# PCB-GONIO-V2.net
KiCad netlist of a schematic drawn in EAGLE
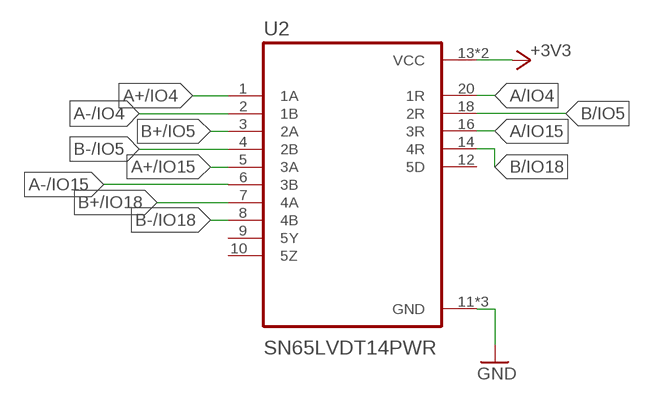
[diagram p0: schematic, sheet 1, part 1 of 2]
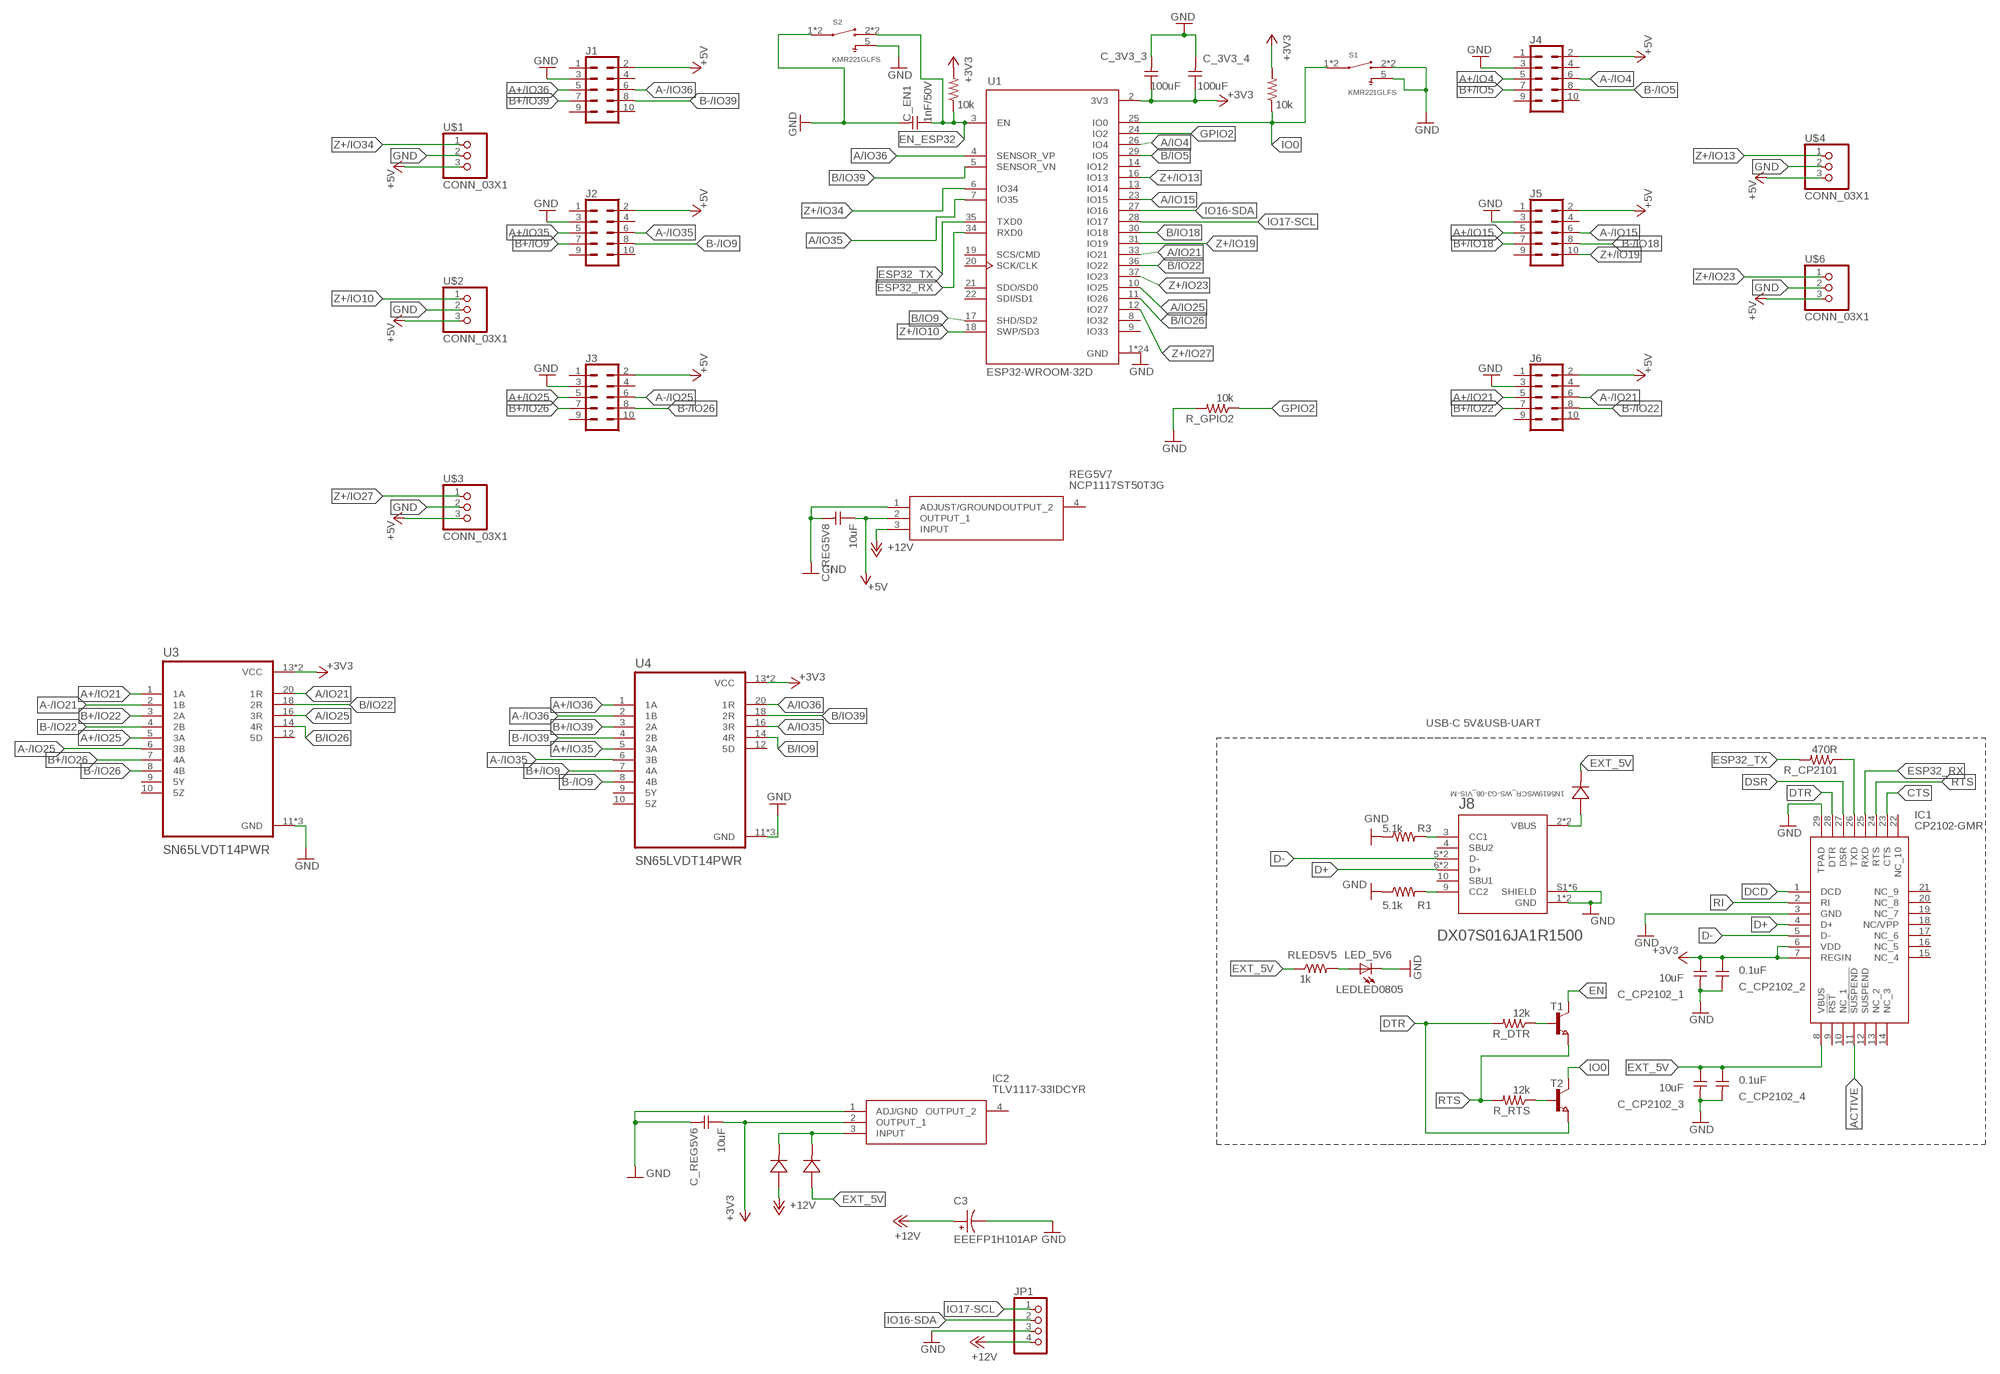
[diagram p1: schematic, sheet 1, part 2 of 2]

(export (version "E")
  (design (tool "Eeschema 10.0.6"))
  (components
    (comp (ref "C3")
      (value "EEEFP1H101AP")
      (footprint "eagle-import:CAP_EEEFP1H101AP")
      (fields (field (name "DIGIKEY_PART_NUMBER") "P19726TR-ND") (field (name "MF") "Panasonic"))
      (libsource (lib "eagle-import") (part "EEEFP1H101AP"))
    )
    (comp (ref "CR1")
      (value "1N5819WSCR_WS-G3-08_VIS-M")
      (footprint "eagle-import:CR_WS-G3-08_VIS-M")
      (fields
        (field (name "MANUFACTURER_PART_NUMBER") "1N4148WS-G3-08")
        (field (name "COPYRIGHT") "Copyright (C) 2022 Ultra Librarian. All rights reserved.")
      )
      (libsource (lib "eagle-import") (part "1N5819WSCR_WS-G3-08_VIS-M"))
    )
    (comp (ref "CR2")
      (value "1N5819WSCR_WS-G3-08_VIS-M")
      (footprint "eagle-import:CR_WS-G3-08_VIS-M")
      (fields
        (field (name "MANUFACTURER_PART_NUMBER") "1N4148WS-G3-08")
        (field (name "COPYRIGHT") "Copyright (C) 2022 Ultra Librarian. All rights reserved.")
      )
      (libsource (lib "eagle-import") (part "1N5819WSCR_WS-G3-08_VIS-M"))
    )
    (comp (ref "CR3")
      (value "1N5819WSCR_WS-G3-08_VIS-M")
      (footprint "eagle-import:CR_WS-G3-08_VIS-M")
      (fields
        (field (name "MANUFACTURER_PART_NUMBER") "1N4148WS-G3-08")
        (field (name "COPYRIGHT") "Copyright (C) 2022 Ultra Librarian. All rights reserved.")
      )
      (libsource (lib "eagle-import") (part "1N5819WSCR_WS-G3-08_VIS-M"))
    )
    (comp (ref "C_3V3_3")
      (value "100uF")
      (footprint "eagle-import:C1206FAB")
      (libsource (lib "eagle-import") (part "CAP_UNPOLARIZEDFAB"))
    )
    (comp (ref "C_3V3_4")
      (value "100uF")
      (footprint "eagle-import:C1206FAB")
      (libsource (lib "eagle-import") (part "CAP_UNPOLARIZEDFAB"))
    )
    (comp (ref "C_CP2102_1")
      (value "10uF")
      (footprint "eagle-import:C1206FAB")
      (libsource (lib "eagle-import") (part "CAP_UNPOLARIZEDFAB"))
    )
    (comp (ref "C_CP2102_2")
      (value "0.1uF")
      (footprint "eagle-import:C1206FAB")
      (libsource (lib "eagle-import") (part "CAP_UNPOLARIZEDFAB"))
    )
    (comp (ref "C_CP2102_3")
      (value "10uF")
      (footprint "eagle-import:C1206FAB")
      (libsource (lib "eagle-import") (part "CAP_UNPOLARIZEDFAB"))
    )
    (comp (ref "C_CP2102_4")
      (value "0.1uF")
      (footprint "eagle-import:C1206FAB")
      (libsource (lib "eagle-import") (part "CAP_UNPOLARIZEDFAB"))
    )
    (comp (ref "C_EN1")
      (value "1nF/50V")
      (footprint "eagle-import:C1206FAB")
      (libsource (lib "eagle-import") (part "CAP_UNPOLARIZEDFAB"))
    )
    (comp (ref "C_REG5V6")
      (value "10uF")
      (footprint "eagle-import:C1206FAB")
      (libsource (lib "eagle-import") (part "CAP_UNPOLARIZEDFAB"))
    )
    (comp (ref "C_REG5V8")
      (value "10uF")
      (footprint "eagle-import:C1206FAB")
      (libsource (lib "eagle-import") (part "CAP_UNPOLARIZEDFAB"))
    )
    (comp (ref "IC1")
      (value "CP2102-GMR")
      (footprint "eagle-import:QFN50P500X500X100-29N")
      (fields (field (name "MOUSER_PART_NUMBER") "634-CP2102-GMR"))
      (libsource (lib "eagle-import") (part "CP2102-GMR"))
    )
    (comp (ref "IC2")
      (value "TLV1117-33IDCYR")
      (footprint "eagle-import:SOT230P700X180-4N")
      (fields (field (name "MOUSER_PART_NUMBER") "595-TLV1117-33IDCYR"))
      (libsource (lib "eagle-import") (part "TLV1117-33IDCYR"))
    )
    (comp (ref "J1")
      (value "CONN_05X2SHD")
      (footprint "eagle-import:2X5-SHROUDED")
      (libsource (lib "eagle-import") (part "CONN_05X2SHD"))
    )
    (comp (ref "J2")
      (value "CONN_05X2SHD")
      (footprint "eagle-import:2X5-SHROUDED")
      (libsource (lib "eagle-import") (part "CONN_05X2SHD"))
    )
    (comp (ref "J3")
      (value "CONN_05X2SHD")
      (footprint "eagle-import:2X5-SHROUDED")
      (libsource (lib "eagle-import") (part "CONN_05X2SHD"))
    )
    (comp (ref "J4")
      (value "CONN_05X2SHD")
      (footprint "eagle-import:2X5-SHROUDED")
      (libsource (lib "eagle-import") (part "CONN_05X2SHD"))
    )
    (comp (ref "J5")
      (value "CONN_05X2SHD")
      (footprint "eagle-import:2X5-SHROUDED")
      (libsource (lib "eagle-import") (part "CONN_05X2SHD"))
    )
    (comp (ref "J6")
      (value "CONN_05X2SHD")
      (footprint "eagle-import:2X5-SHROUDED")
      (libsource (lib "eagle-import") (part "CONN_05X2SHD"))
    )
    (comp (ref "J8")
      (value "DX07S016JA1R1500")
      (footprint "eagle-import:JAE_DX07S016JA1R1500")
      (fields (field (name "MF") "Japan Aviation Electronics"))
      (libsource (lib "eagle-import") (part "DX07S016JA1R1500"))
    )
    (comp (ref "JP1")
      (value "PINHD-1X4")
      (footprint "eagle-import:1X04")
      (libsource (lib "eagle-import") (part "PINHD-1X4"))
    )
    (comp (ref "LED_5V6")
      (value "LEDLED0805")
      (footprint "eagle-import:LEDC2012X90N")
      (libsource (lib "eagle-import") (part "LEDLED0805"))
    )
    (comp (ref "R1")
      (value "5.1k")
      (footprint "eagle-import:R1206W")
      (libsource (lib "eagle-import") (part "R-US_R1206W"))
    )
    (comp (ref "R3")
      (value "5.1k")
      (footprint "eagle-import:R1206W")
      (libsource (lib "eagle-import") (part "R-US_R1206W"))
    )
    (comp (ref "REG5V7")
      (value "NCP1117ST50T3G")
      (footprint "eagle-import:SOT230P700X180-4N")
      (fields (field (name "LCSC_PART") "C17314") (field (name "RS_PART_NUMBER") "8022130P"))
      (libsource (lib "eagle-import") (part "NCP1117ST50T3G"))
    )
    (comp (ref "RLED5V5")
      (value "1k")
      (footprint "eagle-import:R1206FAB")
      (libsource (lib "eagle-import") (part "R1206FAB"))
    )
    (comp (ref "R_CP2101")
      (value "470R")
      (footprint "eagle-import:R1206FAB")
      (libsource (lib "eagle-import") (part "R1206FAB"))
    )
    (comp (ref "R_DTR")
      (value "12k")
      (footprint "eagle-import:R1206FAB")
      (libsource (lib "eagle-import") (part "R1206FAB"))
    )
    (comp (ref "R_GPIO2")
      (value "10k")
      (footprint "eagle-import:R1206FAB")
      (libsource (lib "eagle-import") (part "R1206FAB"))
    )
    (comp (ref "R_PULL_UP1")
      (value "10k")
      (footprint "eagle-import:R1206FAB")
      (libsource (lib "eagle-import") (part "R1206FAB"))
    )
    (comp (ref "R_PULL_UP3")
      (value "10k")
      (footprint "eagle-import:R1206FAB")
      (libsource (lib "eagle-import") (part "R1206FAB"))
    )
    (comp (ref "R_RTS")
      (value "12k")
      (footprint "eagle-import:R1206FAB")
      (libsource (lib "eagle-import") (part "R1206FAB"))
    )
    (comp (ref "S1")
      (value "KMR221GLFS")
      (footprint "eagle-import:SW_KMR221GLFS")
      (fields (field (name "MF") "C&K"))
      (libsource (lib "eagle-import") (part "KMR221GLFS"))
    )
    (comp (ref "S2")
      (value "KMR221GLFS")
      (footprint "eagle-import:SW_KMR221GLFS")
      (fields (field (name "MF") "C&K"))
      (libsource (lib "eagle-import") (part "KMR221GLFS"))
    )
    (comp (ref "T1")
      (value "T_NPN_S8050-J3Y_CHANGJ_SOT23-BEC")
      (footprint "eagle-import:SOT23")
      (fields (field (name "LCSC_PART") "C2146"))
      (libsource (lib "eagle-import") (part "T_NPN__SOT23-BECS8050-J3Y_CHANGJ"))
    )
    (comp (ref "T2")
      (value "T_NPN_S8050-J3Y_CHANGJ_SOT23-BEC")
      (footprint "eagle-import:SOT23")
      (fields (field (name "LCSC_PART") "C2146"))
      (libsource (lib "eagle-import") (part "T_NPN__SOT23-BECS8050-J3Y_CHANGJ"))
    )
    (comp (ref "U$1")
      (value "CONN_03X1")
      (footprint "eagle-import:1X3")
      (libsource (lib "eagle-import") (part "CONN_03X1"))
    )
    (comp (ref "U$2")
      (value "CONN_03X1")
      (footprint "eagle-import:1X3")
      (libsource (lib "eagle-import") (part "CONN_03X1"))
    )
    (comp (ref "U$3")
      (value "CONN_03X1")
      (footprint "eagle-import:1X3")
      (libsource (lib "eagle-import") (part "CONN_03X1"))
    )
    (comp (ref "U$4")
      (value "CONN_03X1")
      (footprint "eagle-import:1X3")
      (libsource (lib "eagle-import") (part "CONN_03X1"))
    )
    (comp (ref "U$6")
      (value "CONN_03X1")
      (footprint "eagle-import:1X3")
      (libsource (lib "eagle-import") (part "CONN_03X1"))
    )
    (comp (ref "U1")
      (value "ESP32-WROOM-32D")
      (footprint "eagle-import:MODULE_ESP32-WROOM-32D")
      (fields (field (name "MF") "Espressif Systems"))
      (libsource (lib "eagle-import") (part "ESP32-WROOM-32D"))
    )
    (comp (ref "U2")
      (value "SN65LVDT14PWR")
      (footprint "eagle-import:SOP65P640X120-20N")
      (fields (field (name "MF") "Texas Instruments"))
      (libsource (lib "eagle-import") (part "SN65LVDT14PWR"))
    )
    (comp (ref "U3")
      (value "SN65LVDT14PWR")
      (footprint "eagle-import:SOP65P640X120-20N")
      (fields (field (name "MF") "Texas Instruments"))
      (libsource (lib "eagle-import") (part "SN65LVDT14PWR"))
    )
    (comp (ref "U4")
      (value "SN65LVDT14PWR")
      (footprint "eagle-import:SOP65P640X120-20N")
      (fields (field (name "MF") "Texas Instruments"))
      (libsource (lib "eagle-import") (part "SN65LVDT14PWR"))
    )
  )
  (nets
    (net (code "1") (name "+3V3") (class "Default")
      (node (ref "C_3V3_3") (pin "1") (pinfunction "1_1") (pintype "passive"))
      (node (ref "C_3V3_4") (pin "1") (pinfunction "1_1") (pintype "passive"))
      (node (ref "C_CP2102_1") (pin "1") (pinfunction "1_1") (pintype "passive"))
      (node (ref "C_CP2102_2") (pin "1") (pinfunction "1_1") (pintype "passive"))
      (node (ref "C_REG5V6") (pin "1") (pinfunction "1_1") (pintype "passive"))
      (node (ref "IC1") (pin "6") (pinfunction "VDD_6") (pintype "bidirectional"))
      (node (ref "IC1") (pin "7") (pinfunction "REGIN_7") (pintype "bidirectional"))
      (node (ref "IC2") (pin "2") (pinfunction "OUTPUT_1_2") (pintype "bidirectional"))
      (node (ref "R_PULL_UP1") (pin "2") (pinfunction "2_2") (pintype "passive"))
      (node (ref "R_PULL_UP3") (pin "2") (pinfunction "2_2") (pintype "passive"))
      (node (ref "U1") (pin "2") (pinfunction "3V3_2") (pintype "power_in"))
      (node (ref "U2") (pin "13") (pinfunction "VCC_13") (pintype "power_in"))
      (node (ref "U2") (pin "17") (pinfunction "VCC_17") (pintype "power_in"))
      (node (ref "U3") (pin "13") (pinfunction "VCC_13") (pintype "power_in"))
      (node (ref "U3") (pin "17") (pinfunction "VCC_17") (pintype "power_in"))
      (node (ref "U4") (pin "13") (pinfunction "VCC_13") (pintype "power_in"))
      (node (ref "U4") (pin "17") (pinfunction "VCC_17") (pintype "power_in"))
    )
    (net (code "2") (name "+5V") (class "Default")
      (node (ref "C_REG5V8") (pin "1") (pinfunction "1_1") (pintype "passive"))
      (node (ref "J1") (pin "2") (pinfunction "2_2") (pintype "passive"))
      (node (ref "J2") (pin "2") (pinfunction "2_2") (pintype "passive"))
      (node (ref "J3") (pin "2") (pinfunction "2_2") (pintype "passive"))
      (node (ref "J4") (pin "2") (pinfunction "2_2") (pintype "passive"))
      (node (ref "J5") (pin "2") (pinfunction "2_2") (pintype "passive"))
      (node (ref "J6") (pin "2") (pinfunction "2_2") (pintype "passive"))
      (node (ref "REG5V7") (pin "2") (pinfunction "OUTPUT_1_2") (pintype "bidirectional"))
      (node (ref "U$1") (pin "3") (pinfunction "3_3") (pintype "passive"))
      (node (ref "U$2") (pin "3") (pinfunction "3_3") (pintype "passive"))
      (node (ref "U$3") (pin "3") (pinfunction "3_3") (pintype "passive"))
      (node (ref "U$4") (pin "3") (pinfunction "3_3") (pintype "passive"))
      (node (ref "U$6") (pin "3") (pinfunction "3_3") (pintype "passive"))
    )
    (net (code "3") (name "+12V") (class "Default")
      (node (ref "C3") (pin "1") (pinfunction "1_1") (pintype "passive"))
      (node (ref "CR2") (pin "2") (pinfunction "2_2") (pintype "passive"))
      (node (ref "JP1") (pin "4") (pinfunction "4_4") (pintype "passive"))
      (node (ref "REG5V7") (pin "3") (pinfunction "INPUT_3") (pintype "bidirectional"))
    )
    (net (code "4") (name "A+{slash}IO4") (class "Default")
      (node (ref "J4") (pin "5") (pinfunction "5_5") (pintype "passive"))
      (node (ref "U2") (pin "1") (pinfunction "1A_1") (pintype "input"))
    )
    (net (code "5") (name "A+{slash}IO15") (class "Default")
      (node (ref "J5") (pin "5") (pinfunction "5_5") (pintype "passive"))
      (node (ref "U2") (pin "5") (pinfunction "3A_5") (pintype "input"))
    )
    (net (code "6") (name "A+{slash}IO21") (class "Default")
      (node (ref "J6") (pin "5") (pinfunction "5_5") (pintype "passive"))
      (node (ref "U3") (pin "1") (pinfunction "1A_1") (pintype "input"))
    )
    (net (code "7") (name "A+{slash}IO25") (class "Default")
      (node (ref "J3") (pin "5") (pinfunction "5_5") (pintype "passive"))
      (node (ref "U3") (pin "5") (pinfunction "3A_5") (pintype "input"))
    )
    (net (code "8") (name "A+{slash}IO35") (class "Default")
      (node (ref "J2") (pin "5") (pinfunction "5_5") (pintype "passive"))
      (node (ref "U4") (pin "5") (pinfunction "3A_5") (pintype "input"))
    )
    (net (code "9") (name "A+{slash}IO36") (class "Default")
      (node (ref "J1") (pin "5") (pinfunction "5_5") (pintype "passive"))
      (node (ref "U4") (pin "1") (pinfunction "1A_1") (pintype "input"))
    )
    (net (code "10") (name "A-{slash}IO4") (class "Default")
      (node (ref "J4") (pin "6") (pinfunction "6_6") (pintype "passive"))
      (node (ref "U2") (pin "2") (pinfunction "1B_2") (pintype "input"))
    )
    (net (code "11") (name "A-{slash}IO15") (class "Default")
      (node (ref "J5") (pin "6") (pinfunction "6_6") (pintype "passive"))
      (node (ref "U2") (pin "6") (pinfunction "3B_6") (pintype "input"))
    )
    (net (code "12") (name "A-{slash}IO21") (class "Default")
      (node (ref "J6") (pin "6") (pinfunction "6_6") (pintype "passive"))
      (node (ref "U3") (pin "2") (pinfunction "1B_2") (pintype "input"))
    )
    (net (code "13") (name "A-{slash}IO25") (class "Default")
      (node (ref "J3") (pin "6") (pinfunction "6_6") (pintype "passive"))
      (node (ref "U3") (pin "6") (pinfunction "3B_6") (pintype "input"))
    )
    (net (code "14") (name "A-{slash}IO35") (class "Default")
      (node (ref "J2") (pin "6") (pinfunction "6_6") (pintype "passive"))
      (node (ref "U4") (pin "6") (pinfunction "3B_6") (pintype "input"))
    )
    (net (code "15") (name "A-{slash}IO36") (class "Default")
      (node (ref "J1") (pin "6") (pinfunction "6_6") (pintype "passive"))
      (node (ref "U4") (pin "2") (pinfunction "1B_2") (pintype "input"))
    )
    (net (code "16") (name "ACTIVE") (class "Default")
      (node (ref "IC1") (pin "11") (pinfunction "~{SUSPEND}_11") (pintype "bidirectional"))
    )
    (net (code "17") (name "A{slash}IO4") (class "Default")
      (node (ref "U1") (pin "26") (pinfunction "IO4_26") (pintype "bidirectional"))
      (node (ref "U2") (pin "20") (pinfunction "1R_20") (pintype "output"))
    )
    (net (code "18") (name "A{slash}IO15") (class "Default")
      (node (ref "U1") (pin "23") (pinfunction "IO15_23") (pintype "bidirectional"))
      (node (ref "U2") (pin "16") (pinfunction "3R_16") (pintype "output"))
    )
    (net (code "19") (name "A{slash}IO21") (class "Default")
      (node (ref "U1") (pin "33") (pinfunction "IO21_33") (pintype "bidirectional"))
      (node (ref "U3") (pin "20") (pinfunction "1R_20") (pintype "output"))
    )
    (net (code "20") (name "A{slash}IO25") (class "Default")
      (node (ref "U1") (pin "10") (pinfunction "IO25_10") (pintype "bidirectional"))
      (node (ref "U3") (pin "16") (pinfunction "3R_16") (pintype "output"))
    )
    (net (code "21") (name "A{slash}IO35") (class "Default")
      (node (ref "U1") (pin "7") (pinfunction "IO35_7") (pintype "input"))
      (node (ref "U4") (pin "16") (pinfunction "3R_16") (pintype "output"))
    )
    (net (code "22") (name "A{slash}IO36") (class "Default")
      (node (ref "U1") (pin "4") (pinfunction "SENSOR_VP_4") (pintype "input"))
      (node (ref "U4") (pin "20") (pinfunction "1R_20") (pintype "output"))
    )
    (net (code "23") (name "B+{slash}IO5") (class "Default")
      (node (ref "J4") (pin "7") (pinfunction "7_7") (pintype "passive"))
      (node (ref "U2") (pin "3") (pinfunction "2A_3") (pintype "input"))
    )
    (net (code "24") (name "B+{slash}IO9") (class "Default")
      (node (ref "J2") (pin "7") (pinfunction "7_7") (pintype "passive"))
      (node (ref "U4") (pin "7") (pinfunction "4A_7") (pintype "input"))
    )
    (net (code "25") (name "B+{slash}IO18") (class "Default")
      (node (ref "J5") (pin "7") (pinfunction "7_7") (pintype "passive"))
      (node (ref "U2") (pin "7") (pinfunction "4A_7") (pintype "input"))
    )
    (net (code "26") (name "B+{slash}IO22") (class "Default")
      (node (ref "J6") (pin "7") (pinfunction "7_7") (pintype "passive"))
      (node (ref "U3") (pin "3") (pinfunction "2A_3") (pintype "input"))
    )
    (net (code "27") (name "B+{slash}IO26") (class "Default")
      (node (ref "J3") (pin "7") (pinfunction "7_7") (pintype "passive"))
      (node (ref "U3") (pin "7") (pinfunction "4A_7") (pintype "input"))
    )
    (net (code "28") (name "B+{slash}IO39") (class "Default")
      (node (ref "J1") (pin "7") (pinfunction "7_7") (pintype "passive"))
      (node (ref "U4") (pin "3") (pinfunction "2A_3") (pintype "input"))
    )
    (net (code "29") (name "B-{slash}IO5") (class "Default")
      (node (ref "J4") (pin "8") (pinfunction "8_8") (pintype "passive"))
      (node (ref "U2") (pin "4") (pinfunction "2B_4") (pintype "input"))
    )
    (net (code "30") (name "B-{slash}IO9") (class "Default")
      (node (ref "J2") (pin "8") (pinfunction "8_8") (pintype "passive"))
      (node (ref "U4") (pin "8") (pinfunction "4B_8") (pintype "input"))
    )
    (net (code "31") (name "B-{slash}IO18") (class "Default")
      (node (ref "J5") (pin "8") (pinfunction "8_8") (pintype "passive"))
      (node (ref "U2") (pin "8") (pinfunction "4B_8") (pintype "input"))
    )
    (net (code "32") (name "B-{slash}IO22") (class "Default")
      (node (ref "J6") (pin "8") (pinfunction "8_8") (pintype "passive"))
      (node (ref "U3") (pin "4") (pinfunction "2B_4") (pintype "input"))
    )
    (net (code "33") (name "B-{slash}IO26") (class "Default")
      (node (ref "J3") (pin "8") (pinfunction "8_8") (pintype "passive"))
      (node (ref "U3") (pin "8") (pinfunction "4B_8") (pintype "input"))
    )
    (net (code "34") (name "B-{slash}IO39") (class "Default")
      (node (ref "J1") (pin "8") (pinfunction "8_8") (pintype "passive"))
      (node (ref "U4") (pin "4") (pinfunction "2B_4") (pintype "input"))
    )
    (net (code "35") (name "B{slash}IO5") (class "Default")
      (node (ref "U1") (pin "29") (pinfunction "IO5_29") (pintype "bidirectional"))
      (node (ref "U2") (pin "18") (pinfunction "2R_18") (pintype "output"))
    )
    (net (code "36") (name "B{slash}IO9") (class "Default")
      (node (ref "U1") (pin "17") (pinfunction "SHD/SD2_17") (pintype "bidirectional"))
      (node (ref "U4") (pin "14") (pinfunction "4R_14") (pintype "output"))
    )
    (net (code "37") (name "B{slash}IO18") (class "Default")
      (node (ref "U1") (pin "30") (pinfunction "IO18_30") (pintype "bidirectional"))
      (node (ref "U2") (pin "14") (pinfunction "4R_14") (pintype "output"))
    )
    (net (code "38") (name "B{slash}IO22") (class "Default")
      (node (ref "U1") (pin "36") (pinfunction "IO22_36") (pintype "bidirectional"))
      (node (ref "U3") (pin "18") (pinfunction "2R_18") (pintype "output"))
    )
    (net (code "39") (name "B{slash}IO26") (class "Default")
      (node (ref "U1") (pin "11") (pinfunction "IO26_11") (pintype "bidirectional"))
      (node (ref "U3") (pin "14") (pinfunction "4R_14") (pintype "output"))
    )
    (net (code "40") (name "B{slash}IO39") (class "Default")
      (node (ref "U1") (pin "5") (pinfunction "SENSOR_VN_5") (pintype "input"))
      (node (ref "U4") (pin "18") (pinfunction "2R_18") (pintype "output"))
    )
    (net (code "41") (name "CTS") (class "Default")
      (node (ref "IC1") (pin "23") (pinfunction "CTS_23") (pintype "bidirectional"))
    )
    (net (code "42") (name "D+") (class "Default")
      (node (ref "IC1") (pin "4") (pinfunction "D+_4") (pintype "bidirectional"))
      (node (ref "J8") (pin "6") (pinfunction "D+_6") (pintype "passive"))
      (node (ref "J8") (pin "7") (pinfunction "D+_7") (pintype "passive"))
    )
    (net (code "43") (name "D-") (class "Default")
      (node (ref "IC1") (pin "5") (pinfunction "D-_5") (pintype "bidirectional"))
      (node (ref "J8") (pin "5") (pinfunction "D-_5") (pintype "passive"))
      (node (ref "J8") (pin "8") (pinfunction "D-_8") (pintype "passive"))
    )
    (net (code "44") (name "DCD") (class "Default")
      (node (ref "IC1") (pin "1") (pinfunction "DCD_1") (pintype "bidirectional"))
    )
    (net (code "45") (name "DSR") (class "Default")
      (node (ref "IC1") (pin "27") (pinfunction "DSR_27") (pintype "bidirectional"))
    )
    (net (code "46") (name "DTR") (class "Default")
      (node (ref "IC1") (pin "28") (pinfunction "DTR_28") (pintype "bidirectional"))
      (node (ref "R_DTR") (pin "2") (pinfunction "2_2") (pintype "passive"))
      (node (ref "T2") (pin "2") (pinfunction "E_2") (pintype "passive"))
    )
    (net (code "47") (name "EN") (class "Default")
      (node (ref "T1") (pin "3") (pinfunction "C_3") (pintype "passive"))
    )
    (net (code "48") (name "EN_ESP32") (class "Default")
      (node (ref "C_EN1") (pin "1") (pinfunction "1_1") (pintype "passive"))
      (node (ref "R_PULL_UP1") (pin "1") (pinfunction "1_1") (pintype "passive"))
      (node (ref "S2") (pin "2") (pinfunction "3_2") (pintype "passive"))
      (node (ref "S2") (pin "3") (pinfunction "3_3") (pintype "passive"))
      (node (ref "U1") (pin "3") (pinfunction "EN_3") (pintype "input"))
    )
    (net (code "49") (name "ESP32_RX") (class "Default")
      (node (ref "IC1") (pin "25") (pinfunction "RXD_25") (pintype "bidirectional"))
      (node (ref "U1") (pin "34") (pinfunction "RXD0_34") (pintype "bidirectional"))
    )
    (net (code "50") (name "ESP32_TX") (class "Default")
      (node (ref "R_CP2101") (pin "2") (pinfunction "2_2") (pintype "passive"))
      (node (ref "U1") (pin "35") (pinfunction "TXD0_35") (pintype "bidirectional"))
    )
    (net (code "51") (name "EXT_5V") (class "Default")
      (node (ref "CR1") (pin "1") (pinfunction "1_1") (pintype "passive"))
      (node (ref "CR3") (pin "2") (pinfunction "2_2") (pintype "passive"))
      (node (ref "C_CP2102_3") (pin "1") (pinfunction "1_1") (pintype "passive"))
      (node (ref "C_CP2102_4") (pin "1") (pinfunction "1_1") (pintype "passive"))
      (node (ref "IC1") (pin "8") (pinfunction "VBUS_8") (pintype "bidirectional"))
      (node (ref "RLED5V5") (pin "1") (pinfunction "1_1") (pintype "passive"))
    )
    (net (code "52") (name "GND") (class "Default")
      (node (ref "C3") (pin "2") (pinfunction "2_2") (pintype "passive"))
      (node (ref "C_3V3_3") (pin "2") (pinfunction "2_2") (pintype "passive"))
      (node (ref "C_3V3_4") (pin "2") (pinfunction "2_2") (pintype "passive"))
      (node (ref "C_CP2102_1") (pin "2") (pinfunction "2_2") (pintype "passive"))
      (node (ref "C_CP2102_2") (pin "2") (pinfunction "2_2") (pintype "passive"))
      (node (ref "C_CP2102_3") (pin "2") (pinfunction "2_2") (pintype "passive"))
      (node (ref "C_CP2102_4") (pin "2") (pinfunction "2_2") (pintype "passive"))
      (node (ref "C_EN1") (pin "2") (pinfunction "2_2") (pintype "passive"))
      (node (ref "C_REG5V6") (pin "2") (pinfunction "2_2") (pintype "passive"))
      (node (ref "C_REG5V8") (pin "2") (pinfunction "2_2") (pintype "passive"))
      (node (ref "IC1") (pin "29") (pinfunction "TPAD_29") (pintype "bidirectional"))
      (node (ref "IC1") (pin "3") (pinfunction "GND_3") (pintype "bidirectional"))
      (node (ref "IC2") (pin "1") (pinfunction "ADJ/GND_1") (pintype "bidirectional"))
      (node (ref "J1") (pin "3") (pinfunction "3_3") (pintype "passive"))
      (node (ref "J2") (pin "3") (pinfunction "3_3") (pintype "passive"))
      (node (ref "J3") (pin "3") (pinfunction "3_3") (pintype "passive"))
      (node (ref "J4") (pin "3") (pinfunction "3_3") (pintype "passive"))
      (node (ref "J5") (pin "3") (pinfunction "3_3") (pintype "passive"))
      (node (ref "J6") (pin "3") (pinfunction "3_3") (pintype "passive"))
      (node (ref "J8") (pin "1") (pinfunction "GND_1") (pintype "power_in"))
      (node (ref "J8") (pin "12") (pinfunction "GND_12") (pintype "power_in"))
      (node (ref "J8") (pin "S1") (pinfunction "SHIELD_S1") (pintype "passive"))
      (node (ref "J8") (pin "S2") (pinfunction "SHIELD_S2") (pintype "passive"))
      (node (ref "J8") (pin "S3") (pinfunction "SHIELD_S3") (pintype "passive"))
      (node (ref "J8") (pin "S4") (pinfunction "SHIELD_S4") (pintype "passive"))
      (node (ref "J8") (pin "S5") (pinfunction "SHIELD_S5") (pintype "passive"))
      (node (ref "J8") (pin "S6") (pinfunction "SHIELD_S6") (pintype "passive"))
      (node (ref "JP1") (pin "3") (pinfunction "3_3") (pintype "passive"))
      (node (ref "LED_5V6") (pin "1") (pinfunction "C_1") (pintype "passive"))
      (node (ref "R1") (pin "1") (pinfunction "1_1") (pintype "passive"))
      (node (ref "R3") (pin "1") (pinfunction "1_1") (pintype "passive"))
      (node (ref "REG5V7") (pin "1") (pinfunction "ADJUST/GROUND_1") (pintype "bidirectional"))
      (node (ref "R_GPIO2") (pin "2") (pinfunction "2_2") (pintype "passive"))
      (node (ref "S1") (pin "2") (pinfunction "3_2") (pintype "passive"))
      (node (ref "S1") (pin "3") (pinfunction "3_3") (pintype "passive"))
      (node (ref "S1") (pin "5") (pinfunction "5_5") (pintype "passive"))
      (node (ref "S2") (pin "1") (pinfunction "1_1") (pintype "passive"))
      (node (ref "S2") (pin "4") (pinfunction "1_4") (pintype "passive"))
      (node (ref "S2") (pin "5") (pinfunction "5_5") (pintype "passive"))
      (node (ref "U$1") (pin "2") (pinfunction "2_2") (pintype "passive"))
      (node (ref "U$2") (pin "2") (pinfunction "2_2") (pintype "passive"))
      (node (ref "U$3") (pin "2") (pinfunction "2_2") (pintype "passive"))
      (node (ref "U$4") (pin "2") (pinfunction "2_2") (pintype "passive"))
      (node (ref "U$6") (pin "2") (pinfunction "2_2") (pintype "passive"))
      (node (ref "U1") (pin "1") (pinfunction "GND_1") (pintype "power_in"))
      (node (ref "U1") (pin "15") (pinfunction "GND_15") (pintype "power_in"))
      (node (ref "U1") (pin "38") (pinfunction "GND_38") (pintype "power_in"))
      (node (ref "U1") (pin "39_1") (pinfunction "GND_39_1") (pintype "power_in"))
      (node (ref "U1") (pin "39_10") (pinfunction "GND_39_10") (pintype "power_in"))
      (node (ref "U1") (pin "39_11") (pinfunction "GND_39_11") (pintype "power_in"))
      (node (ref "U1") (pin "39_12") (pinfunction "GND_39_12") (pintype "power_in"))
      (node (ref "U1") (pin "39_13") (pinfunction "GND_39_13") (pintype "power_in"))
      (node (ref "U1") (pin "39_14") (pinfunction "GND_39_14") (pintype "power_in"))
      (node (ref "U1") (pin "39_15") (pinfunction "GND_39_15") (pintype "power_in"))
      (node (ref "U1") (pin "39_16") (pinfunction "GND_39_16") (pintype "power_in"))
      (node (ref "U1") (pin "39_17") (pinfunction "GND_39_17") (pintype "power_in"))
      (node (ref "U1") (pin "39_18") (pinfunction "GND_39_18") (pintype "power_in"))
      (node (ref "U1") (pin "39_19") (pinfunction "GND_39_19") (pintype "power_in"))
      (node (ref "U1") (pin "39_2") (pinfunction "GND_39_2") (pintype "power_in"))
      (node (ref "U1") (pin "39_20") (pinfunction "GND_39_20") (pintype "power_in"))
      (node (ref "U1") (pin "39_21") (pinfunction "GND_39_21") (pintype "power_in"))
      (node (ref "U1") (pin "39_3") (pinfunction "GND_39_3") (pintype "power_in"))
      (node (ref "U1") (pin "39_4") (pinfunction "GND_39_4") (pintype "power_in"))
      (node (ref "U1") (pin "39_5") (pinfunction "GND_39_5") (pintype "power_in"))
      (node (ref "U1") (pin "39_6") (pinfunction "GND_39_6") (pintype "power_in"))
      (node (ref "U1") (pin "39_7") (pinfunction "GND_39_7") (pintype "power_in"))
      (node (ref "U1") (pin "39_8") (pinfunction "GND_39_8") (pintype "power_in"))
      (node (ref "U1") (pin "39_9") (pinfunction "GND_39_9") (pintype "power_in"))
      (node (ref "U2") (pin "11") (pinfunction "GND_11") (pintype "power_in"))
      (node (ref "U2") (pin "15") (pinfunction "GND_15") (pintype "power_in"))
      (node (ref "U2") (pin "19") (pinfunction "GND_19") (pintype "power_in"))
      (node (ref "U3") (pin "11") (pinfunction "GND_11") (pintype "power_in"))
      (node (ref "U3") (pin "15") (pinfunction "GND_15") (pintype "power_in"))
      (node (ref "U3") (pin "19") (pinfunction "GND_19") (pintype "power_in"))
      (node (ref "U4") (pin "11") (pinfunction "GND_11") (pintype "power_in"))
      (node (ref "U4") (pin "15") (pinfunction "GND_15") (pintype "power_in"))
      (node (ref "U4") (pin "19") (pinfunction "GND_19") (pintype "power_in"))
    )
    (net (code "53") (name "GPIO2") (class "Default")
      (node (ref "R_GPIO2") (pin "1") (pinfunction "1_1") (pintype "passive"))
      (node (ref "U1") (pin "24") (pinfunction "IO2_24") (pintype "bidirectional"))
    )
    (net (code "54") (name "IO0") (class "Default")
      (node (ref "R_PULL_UP3") (pin "1") (pinfunction "1_1") (pintype "passive"))
      (node (ref "S1") (pin "1") (pinfunction "1_1") (pintype "passive"))
      (node (ref "S1") (pin "4") (pinfunction "1_4") (pintype "passive"))
      (node (ref "T2") (pin "3") (pinfunction "C_3") (pintype "passive"))
      (node (ref "U1") (pin "25") (pinfunction "IO0_25") (pintype "bidirectional"))
    )
    (net (code "55") (name "IO16-SDA") (class "Default")
      (node (ref "JP1") (pin "2") (pinfunction "2_2") (pintype "passive"))
      (node (ref "U1") (pin "27") (pinfunction "IO16_27") (pintype "bidirectional"))
    )
    (net (code "56") (name "IO17-SCL") (class "Default")
      (node (ref "JP1") (pin "1") (pinfunction "1_1") (pintype "passive"))
      (node (ref "U1") (pin "28") (pinfunction "IO17_28") (pintype "bidirectional"))
    )
    (net (code "57") (name "Net-(CR1-Pad2)") (class "Default")
      (node (ref "CR1") (pin "2") (pinfunction "2_2") (pintype "passive"))
      (node (ref "J8") (pin "11") (pinfunction "VBUS_11") (pintype "power_in"))
      (node (ref "J8") (pin "2") (pinfunction "VBUS_2") (pintype "power_in"))
    )
    (net (code "58") (name "Net-(IC1-TXD)") (class "Default")
      (node (ref "IC1") (pin "26") (pinfunction "TXD_26") (pintype "bidirectional"))
      (node (ref "R_CP2101") (pin "1") (pinfunction "1_1") (pintype "passive"))
    )
    (net (code "59") (name "Net-(IC2-INPUT)") (class "Default")
      (node (ref "CR2") (pin "1") (pinfunction "1_1") (pintype "passive"))
      (node (ref "CR3") (pin "1") (pinfunction "1_1") (pintype "passive"))
      (node (ref "IC2") (pin "3") (pinfunction "INPUT_3") (pintype "bidirectional"))
    )
    (net (code "60") (name "Net-(J8-CC1)") (class "Default")
      (node (ref "J8") (pin "3") (pinfunction "CC1_3") (pintype "passive"))
      (node (ref "R3") (pin "2") (pinfunction "2_2") (pintype "passive"))
    )
    (net (code "61") (name "Net-(J8-CC2)") (class "Default")
      (node (ref "J8") (pin "9") (pinfunction "CC2_9") (pintype "passive"))
      (node (ref "R1") (pin "2") (pinfunction "2_2") (pintype "passive"))
    )
    (net (code "62") (name "Net-(LED_5V6-A)") (class "Default")
      (node (ref "LED_5V6") (pin "2") (pinfunction "A_2") (pintype "passive"))
      (node (ref "RLED5V5") (pin "2") (pinfunction "2_2") (pintype "passive"))
    )
    (net (code "63") (name "Net-(T1-B)") (class "Default")
      (node (ref "R_DTR") (pin "1") (pinfunction "1_1") (pintype "passive"))
      (node (ref "T1") (pin "1") (pinfunction "B_1") (pintype "passive"))
    )
    (net (code "64") (name "Net-(T2-B)") (class "Default")
      (node (ref "R_RTS") (pin "1") (pinfunction "1_1") (pintype "passive"))
      (node (ref "T2") (pin "1") (pinfunction "B_1") (pintype "passive"))
    )
    (net (code "65") (name "RI") (class "Default")
      (node (ref "IC1") (pin "2") (pinfunction "RI_2") (pintype "bidirectional"))
    )
    (net (code "66") (name "RTS") (class "Default")
      (node (ref "IC1") (pin "24") (pinfunction "RTS_24") (pintype "bidirectional"))
      (node (ref "R_RTS") (pin "2") (pinfunction "2_2") (pintype "passive"))
      (node (ref "T1") (pin "2") (pinfunction "E_2") (pintype "passive"))
    )
    (net (code "67") (name "Z+{slash}IO10") (class "Default")
      (node (ref "U$2") (pin "1") (pinfunction "1_1") (pintype "passive"))
      (node (ref "U1") (pin "18") (pinfunction "SWP/SD3_18") (pintype "bidirectional"))
    )
    (net (code "68") (name "Z+{slash}IO13") (class "Default")
      (node (ref "U$4") (pin "1") (pinfunction "1_1") (pintype "passive"))
      (node (ref "U1") (pin "16") (pinfunction "IO13_16") (pintype "bidirectional"))
    )
    (net (code "69") (name "Z+{slash}IO19") (class "Default")
      (node (ref "J5") (pin "10") (pinfunction "10_10") (pintype "passive"))
      (node (ref "U1") (pin "31") (pinfunction "IO19_31") (pintype "bidirectional"))
    )
    (net (code "70") (name "Z+{slash}IO23") (class "Default")
      (node (ref "U$6") (pin "1") (pinfunction "1_1") (pintype "passive"))
      (node (ref "U1") (pin "37") (pinfunction "IO23_37") (pintype "bidirectional"))
    )
    (net (code "71") (name "Z+{slash}IO27") (class "Default")
      (node (ref "U$3") (pin "1") (pinfunction "1_1") (pintype "passive"))
      (node (ref "U1") (pin "12") (pinfunction "IO27_12") (pintype "bidirectional"))
    )
    (net (code "72") (name "Z+{slash}IO34") (class "Default")
      (node (ref "U$1") (pin "1") (pinfunction "1_1") (pintype "passive"))
      (node (ref "U1") (pin "6") (pinfunction "IO34_6") (pintype "input"))
    )
    (net (code "73") (name "unconnected-(IC1-NC_1-Pad10)") (class "Default")
      (node (ref "IC1") (pin "10") (pinfunction "NC_1_10") (pintype "bidirectional"))
    )
    (net (code "74") (name "unconnected-(IC1-NC_2-Pad13)") (class "Default")
      (node (ref "IC1") (pin "13") (pinfunction "NC_2_13") (pintype "bidirectional"))
    )
    (net (code "75") (name "unconnected-(IC1-NC_3-Pad14)") (class "Default")
      (node (ref "IC1") (pin "14") (pinfunction "NC_3_14") (pintype "bidirectional"))
    )
    (net (code "76") (name "unconnected-(IC1-NC_4-Pad15)") (class "Default")
      (node (ref "IC1") (pin "15") (pinfunction "NC_4_15") (pintype "bidirectional"))
    )
    (net (code "77") (name "unconnected-(IC1-NC_5-Pad16)") (class "Default")
      (node (ref "IC1") (pin "16") (pinfunction "NC_5_16") (pintype "bidirectional"))
    )
    (net (code "78") (name "unconnected-(IC1-NC_6-Pad17)") (class "Default")
      (node (ref "IC1") (pin "17") (pinfunction "NC_6_17") (pintype "bidirectional"))
    )
    (net (code "79") (name "unconnected-(IC1-NC_7-Pad19)") (class "Default")
      (node (ref "IC1") (pin "19") (pinfunction "NC_7_19") (pintype "bidirectional"))
    )
    (net (code "80") (name "unconnected-(IC1-NC_8-Pad20)") (class "Default")
      (node (ref "IC1") (pin "20") (pinfunction "NC_8_20") (pintype "bidirectional"))
    )
    (net (code "81") (name "unconnected-(IC1-NC_9-Pad21)") (class "Default")
      (node (ref "IC1") (pin "21") (pinfunction "NC_9_21") (pintype "bidirectional"))
    )
    (net (code "82") (name "unconnected-(IC1-NC_10-Pad22)") (class "Default")
      (node (ref "IC1") (pin "22") (pinfunction "NC_10_22") (pintype "bidirectional"))
    )
    (net (code "83") (name "unconnected-(IC1-NC{slash}VPP-Pad18)") (class "Default")
      (node (ref "IC1") (pin "18") (pinfunction "NC/VPP_18") (pintype "bidirectional"))
    )
    (net (code "84") (name "unconnected-(IC1-SUSPEND-Pad12)") (class "Default")
      (node (ref "IC1") (pin "12") (pinfunction "SUSPEND_12") (pintype "bidirectional"))
    )
    (net (code "85") (name "unconnected-(IC1-~{RST}-Pad9)") (class "Default")
      (node (ref "IC1") (pin "9") (pinfunction "~{RST}_9") (pintype "bidirectional"))
    )
    (net (code "86") (name "unconnected-(IC2-OUTPUT_2-Pad4)") (class "Default")
      (node (ref "IC2") (pin "4") (pinfunction "OUTPUT_2_4") (pintype "bidirectional"))
    )
    (net (code "87") (name "unconnected-(J1-Pad1)") (class "Default")
      (node (ref "J1") (pin "1") (pinfunction "1_1") (pintype "passive"))
    )
    (net (code "88") (name "unconnected-(J1-Pad4)") (class "Default")
      (node (ref "J1") (pin "4") (pinfunction "4_4") (pintype "passive"))
    )
    (net (code "89") (name "unconnected-(J1-Pad9)") (class "Default")
      (node (ref "J1") (pin "9") (pinfunction "9_9") (pintype "passive"))
    )
    (net (code "90") (name "unconnected-(J1-Pad10)") (class "Default")
      (node (ref "J1") (pin "10") (pinfunction "10_10") (pintype "passive"))
    )
    (net (code "91") (name "unconnected-(J2-Pad1)") (class "Default")
      (node (ref "J2") (pin "1") (pinfunction "1_1") (pintype "passive"))
    )
    (net (code "92") (name "unconnected-(J2-Pad4)") (class "Default")
      (node (ref "J2") (pin "4") (pinfunction "4_4") (pintype "passive"))
    )
    (net (code "93") (name "unconnected-(J2-Pad9)") (class "Default")
      (node (ref "J2") (pin "9") (pinfunction "9_9") (pintype "passive"))
    )
    (net (code "94") (name "unconnected-(J2-Pad10)") (class "Default")
      (node (ref "J2") (pin "10") (pinfunction "10_10") (pintype "passive"))
    )
    (net (code "95") (name "unconnected-(J3-Pad1)") (class "Default")
      (node (ref "J3") (pin "1") (pinfunction "1_1") (pintype "passive"))
    )
    (net (code "96") (name "unconnected-(J3-Pad4)") (class "Default")
      (node (ref "J3") (pin "4") (pinfunction "4_4") (pintype "passive"))
    )
    (net (code "97") (name "unconnected-(J3-Pad9)") (class "Default")
      (node (ref "J3") (pin "9") (pinfunction "9_9") (pintype "passive"))
    )
    (net (code "98") (name "unconnected-(J3-Pad10)") (class "Default")
      (node (ref "J3") (pin "10") (pinfunction "10_10") (pintype "passive"))
    )
    (net (code "99") (name "unconnected-(J4-Pad1)") (class "Default")
      (node (ref "J4") (pin "1") (pinfunction "1_1") (pintype "passive"))
    )
    (net (code "100") (name "unconnected-(J4-Pad4)") (class "Default")
      (node (ref "J4") (pin "4") (pinfunction "4_4") (pintype "passive"))
    )
    (net (code "101") (name "unconnected-(J4-Pad9)") (class "Default")
      (node (ref "J4") (pin "9") (pinfunction "9_9") (pintype "passive"))
    )
    (net (code "102") (name "unconnected-(J4-Pad10)") (class "Default")
      (node (ref "J4") (pin "10") (pinfunction "10_10") (pintype "passive"))
    )
    (net (code "103") (name "unconnected-(J5-Pad1)") (class "Default")
      (node (ref "J5") (pin "1") (pinfunction "1_1") (pintype "passive"))
    )
    (net (code "104") (name "unconnected-(J5-Pad4)") (class "Default")
      (node (ref "J5") (pin "4") (pinfunction "4_4") (pintype "passive"))
    )
    (net (code "105") (name "unconnected-(J5-Pad9)") (class "Default")
      (node (ref "J5") (pin "9") (pinfunction "9_9") (pintype "passive"))
    )
    (net (code "106") (name "unconnected-(J6-Pad1)") (class "Default")
      (node (ref "J6") (pin "1") (pinfunction "1_1") (pintype "passive"))
    )
    (net (code "107") (name "unconnected-(J6-Pad4)") (class "Default")
      (node (ref "J6") (pin "4") (pinfunction "4_4") (pintype "passive"))
    )
    (net (code "108") (name "unconnected-(J6-Pad9)") (class "Default")
      (node (ref "J6") (pin "9") (pinfunction "9_9") (pintype "passive"))
    )
    (net (code "109") (name "unconnected-(J6-Pad10)") (class "Default")
      (node (ref "J6") (pin "10") (pinfunction "10_10") (pintype "passive"))
    )
    (net (code "110") (name "unconnected-(J8-SBU1-Pad10)") (class "Default")
      (node (ref "J8") (pin "10") (pinfunction "SBU1_10") (pintype "passive"))
    )
    (net (code "111") (name "unconnected-(J8-SBU2-Pad4)") (class "Default")
      (node (ref "J8") (pin "4") (pinfunction "SBU2_4") (pintype "passive"))
    )
    (net (code "112") (name "unconnected-(REG5V7-OUTPUT_2-Pad4)") (class "Default")
      (node (ref "REG5V7") (pin "4") (pinfunction "OUTPUT_2_4") (pintype "bidirectional"))
    )
    (net (code "113") (name "unconnected-(U1-IO12-Pad14)") (class "Default")
      (node (ref "U1") (pin "14") (pinfunction "IO12_14") (pintype "bidirectional"))
    )
    (net (code "114") (name "unconnected-(U1-IO14-Pad13)") (class "Default")
      (node (ref "U1") (pin "13") (pinfunction "IO14_13") (pintype "bidirectional"))
    )
    (net (code "115") (name "unconnected-(U1-IO32-Pad8)") (class "Default")
      (node (ref "U1") (pin "8") (pinfunction "IO32_8") (pintype "bidirectional"))
    )
    (net (code "116") (name "unconnected-(U1-IO33-Pad9)") (class "Default")
      (node (ref "U1") (pin "9") (pinfunction "IO33_9") (pintype "bidirectional"))
    )
    (net (code "117") (name "unconnected-(U1-SCK{slash}CLK-Pad20)") (class "Default")
      (node (ref "U1") (pin "20") (pinfunction "SCK/CLK_20") (pintype "bidirectional"))
    )
    (net (code "118") (name "unconnected-(U1-SCS{slash}CMD-Pad19)") (class "Default")
      (node (ref "U1") (pin "19") (pinfunction "SCS/CMD_19") (pintype "bidirectional"))
    )
    (net (code "119") (name "unconnected-(U1-SDI{slash}SD1-Pad22)") (class "Default")
      (node (ref "U1") (pin "22") (pinfunction "SDI/SD1_22") (pintype "bidirectional"))
    )
    (net (code "120") (name "unconnected-(U1-SDO{slash}SD0-Pad21)") (class "Default")
      (node (ref "U1") (pin "21") (pinfunction "SDO/SD0_21") (pintype "bidirectional"))
    )
    (net (code "121") (name "unconnected-(U2-5D-Pad12)") (class "Default")
      (node (ref "U2") (pin "12") (pinfunction "5D_12") (pintype "output"))
    )
    (net (code "122") (name "unconnected-(U2-5Y-Pad9)") (class "Default")
      (node (ref "U2") (pin "9") (pinfunction "5Y_9") (pintype "input"))
    )
    (net (code "123") (name "unconnected-(U2-5Z-Pad10)") (class "Default")
      (node (ref "U2") (pin "10") (pinfunction "5Z_10") (pintype "input"))
    )
    (net (code "124") (name "unconnected-(U3-5D-Pad12)") (class "Default")
      (node (ref "U3") (pin "12") (pinfunction "5D_12") (pintype "output"))
    )
    (net (code "125") (name "unconnected-(U3-5Y-Pad9)") (class "Default")
      (node (ref "U3") (pin "9") (pinfunction "5Y_9") (pintype "input"))
    )
    (net (code "126") (name "unconnected-(U3-5Z-Pad10)") (class "Default")
      (node (ref "U3") (pin "10") (pinfunction "5Z_10") (pintype "input"))
    )
    (net (code "127") (name "unconnected-(U4-5D-Pad12)") (class "Default")
      (node (ref "U4") (pin "12") (pinfunction "5D_12") (pintype "output"))
    )
    (net (code "128") (name "unconnected-(U4-5Y-Pad9)") (class "Default")
      (node (ref "U4") (pin "9") (pinfunction "5Y_9") (pintype "input"))
    )
    (net (code "129") (name "unconnected-(U4-5Z-Pad10)") (class "Default")
      (node (ref "U4") (pin "10") (pinfunction "5Z_10") (pintype "input"))
    )
  )
)
